# wheatstone_bridge.net
KiCad netlist of a schematic drawn in Altium Designer
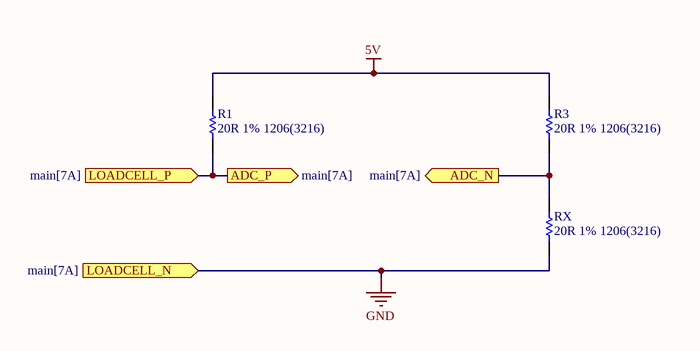
[diagram p0: wheatstone_bridge.SchDoc]

(export (version "E")
  (design (tool "Eeschema 10.0.6"))
  (components
    (comp (ref "R1")
      (value "20R 1% 1206(3216)")
      (footprint "RESC1206(3216)_M")
      (description "20R 0.25W 1% 1206 (3216 Metric)  SMD")
      (fields (field (name "TOLERANCE") "1 %") (field (name "POWER") "0.25 W"))
      (libsource (lib "Altium Content Vault") (part "RES"))
    )
    (comp (ref "R3")
      (value "20R 1% 1206(3216)")
      (footprint "RESC1206(3216)_M")
      (description "20R 0.25W 1% 1206 (3216 Metric)  SMD")
      (fields (field (name "TOLERANCE") "1 %") (field (name "POWER") "0.25 W"))
      (libsource (lib "Altium Content Vault") (part "RES"))
    )
    (comp (ref "RX")
      (value "20R 1% 1206(3216)")
      (footprint "RESC1206(3216)_M")
      (description "20R 0.25W 1% 1206 (3216 Metric)  SMD")
      (fields (field (name "TOLERANCE") "1 %") (field (name "POWER") "0.25 W"))
      (libsource (lib "Altium Content Vault") (part "RES"))
    )
  )
  (nets
    (net (code "1") (name "/ADC_N") (class "Default")
      (node (ref "R3") (pin "1") (pinfunction "1_1") (pintype "passive"))
      (node (ref "RX") (pin "2") (pinfunction "2_2") (pintype "passive"))
    )
    (net (code "2") (name "/ADC_P") (class "Default")
      (node (ref "R1") (pin "1") (pinfunction "1_1") (pintype "passive"))
    )
    (net (code "3") (name "5V") (class "Default")
      (node (ref "R1") (pin "2") (pinfunction "2_2") (pintype "passive"))
      (node (ref "R3") (pin "2") (pinfunction "2_2") (pintype "passive"))
    )
    (net (code "4") (name "GND") (class "Default")
      (node (ref "RX") (pin "1") (pinfunction "1_1") (pintype "passive"))
    )
  )
)
